# 06D_dualDesign.net
KiCad netlist of a schematic drawn in Altium Designer
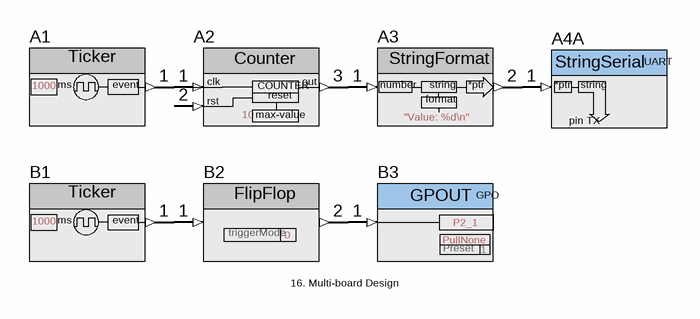
[diagram p0: 06D_dualDesign.SchDoc]

(export (version "E")
  (design (tool "Eeschema 10.0.6"))
  (components
    (comp (ref "A1")
      (value "Ticker")
      (description "Creates a Periodical Event")
      (fields (field (name "NBLOCKSPARAMETER1") "1000"))
      (libsource (lib "studio") (part "NODE-TICKER"))
    )
    (comp (ref "A2")
      (value "Counter")
      (description "Ressetable Counter. Returns to zero, when max-value is reached")
      (fields (field (name "NBLOCKSPARAMETER1") "10"))
      (libsource (lib "studio") (part "NODE-COUNTER"))
    )
    (comp (ref "A3")
      (value "StringFormat")
      (fields (field (name "NBLOCKSPARAMETER1") "\"Value: %~{d}n\""))
      (libsource (lib "studio") (part "NODE-STRINGFORMAT"))
    )
    (comp (ref "A4") (value "StringSerial") (libsource (lib "studio") (part "NODE-STRINGSERIAL-split")))
    (comp (ref "B1")
      (value "Ticker")
      (description "Creates a Periodical Event")
      (fields (field (name "NBLOCKSPARAMETER1") "1000"))
      (libsource (lib "studio") (part "NODE-TICKER"))
    )
    (comp (ref "B2")
      (value "FlipFlop")
      (fields (field (name "PARAMETER 1") "triggerMode") (field (name "NBLOCKSPARAMETER1") "0"))
      (libsource (lib "studio") (part "NODE-FLIPFLOP"))
    )
    (comp (ref "B3")
      (value "GPOUT")
      (description "General Purpose Mcroprocessor Output, set modeString as: PullUp, PullDown, PullNone, OpenDrain")
      (fields
        (field (name "NBLOCKSPARAMETER1") "P2_1")
        (field (name "PARAMETER 3") "Preset")
        (field (name "NBLOCKSPARAMETER3") "1")
        (field (name "NBLOCKSPARAMETER2") "PullNone")
      )
      (libsource (lib "studio") (part "NODE-GPOUT"))
    )
  )
  (nets
    (net (code "1") (name "Net-(A1-OUT)") (class "Default")
      (node (ref "A1") (pin "1") (pinfunction "OUT_1") (pintype "output"))
      (node (ref "A2") (pin "1") (pinfunction "COUNT-IN_1") (pintype "input"))
    )
    (net (code "2") (name "Net-(A2-OUT)") (class "Default")
      (node (ref "A2") (pin "3") (pinfunction "OUT_3") (pintype "output"))
      (node (ref "A3") (pin "1") (pinfunction "IN_1") (pintype "input"))
    )
    (net (code "3") (name "Net-(A3-OUT)") (class "Default")
      (node (ref "A3") (pin "2") (pinfunction "OUT_2") (pintype "output"))
      (node (ref "A4") (pin "1") (pinfunction "TX_1") (pintype "input"))
    )
    (net (code "4") (name "Net-(B1-OUT)") (class "Default")
      (node (ref "B1") (pin "1") (pinfunction "OUT_1") (pintype "output"))
      (node (ref "B2") (pin "1") (pinfunction "IN_1") (pintype "input"))
    )
    (net (code "5") (name "Net-(B3-IN)") (class "Default")
      (node (ref "B2") (pin "2") (pinfunction "2_2") (pintype "output"))
      (node (ref "B3") (pin "1") (pinfunction "IN_1") (pintype "input"))
    )
    (net (code "6") (name "unconnected-(A2-RESET-Pad2)") (class "Default")
      (node (ref "A2") (pin "2") (pinfunction "RESET_2") (pintype "input"))
    )
  )
)
